# CAN_Termination_Connector_JST.net
KiCad netlist of a schematic drawn in Altium Designer
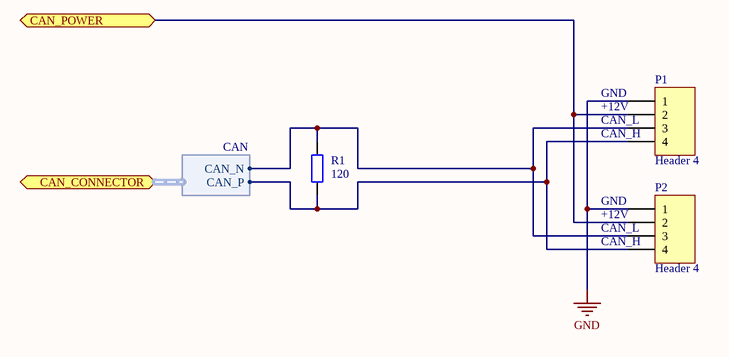
[diagram p0: CAN Termination Connector (JST).SchDoc]

(export (version "E")
  (design (tool "Eeschema 10.0.6"))
  (components
    (comp (ref "P1")
      (value "Header 4")
      (footprint "S04B-PASK-2")
      (description "Header, 4-Pin")
      (fields (field (name "PUBLISHER") "Altium Limited"))
      (libsource (lib "Miscellaneous Connectors") (part "Header 4"))
    )
    (comp (ref "P2")
      (value "Header 4")
      (footprint "S04B-PASK-2")
      (description "Header, 4-Pin")
      (fields (field (name "PUBLISHER") "Altium Limited"))
      (libsource (lib "Miscellaneous Connectors") (part "Header 4"))
    )
    (comp (ref "R1")
      (value "120")
      (footprint "R0603")
      (description "Resistor")
      (fields (field (name "Comment") "Res2") (field (name "PUBLISHER") "Altium Limited"))
      (libsource (lib "Miscellaneous Devices") (part "Res2"))
    )
  )
  (nets
    (net (code "2") (name "/CAN_POWER") (class "Default")
      (node (ref "P1") (pin "2") (pinfunction "2_2") (pintype "passive"))
      (node (ref "P2") (pin "2") (pinfunction "2_2") (pintype "passive"))
    )
    (net (code "4") (name "GND") (class "Default")
      (node (ref "P1") (pin "1") (pinfunction "1_1") (pintype "passive"))
      (node (ref "P2") (pin "1") (pinfunction "1_1") (pintype "passive"))
    )
    (net (code "5") (name "Net-(P1-Pad3)") (class "Default")
      (node (ref "P1") (pin "3") (pinfunction "3_3") (pintype "passive"))
      (node (ref "P2") (pin "3") (pinfunction "3_3") (pintype "passive"))
      (node (ref "R1") (pin "2") (pinfunction "2_2") (pintype "passive"))
    )
    (net (code "6") (name "Net-(P1-Pad4)") (class "Default")
      (node (ref "P1") (pin "4") (pinfunction "4_4") (pintype "passive"))
      (node (ref "P2") (pin "4") (pinfunction "4_4") (pintype "passive"))
      (node (ref "R1") (pin "1") (pinfunction "1_1") (pintype "passive"))
    )
  )
)
